# MCU.net
KiCad netlist of a schematic drawn in Altium Designer
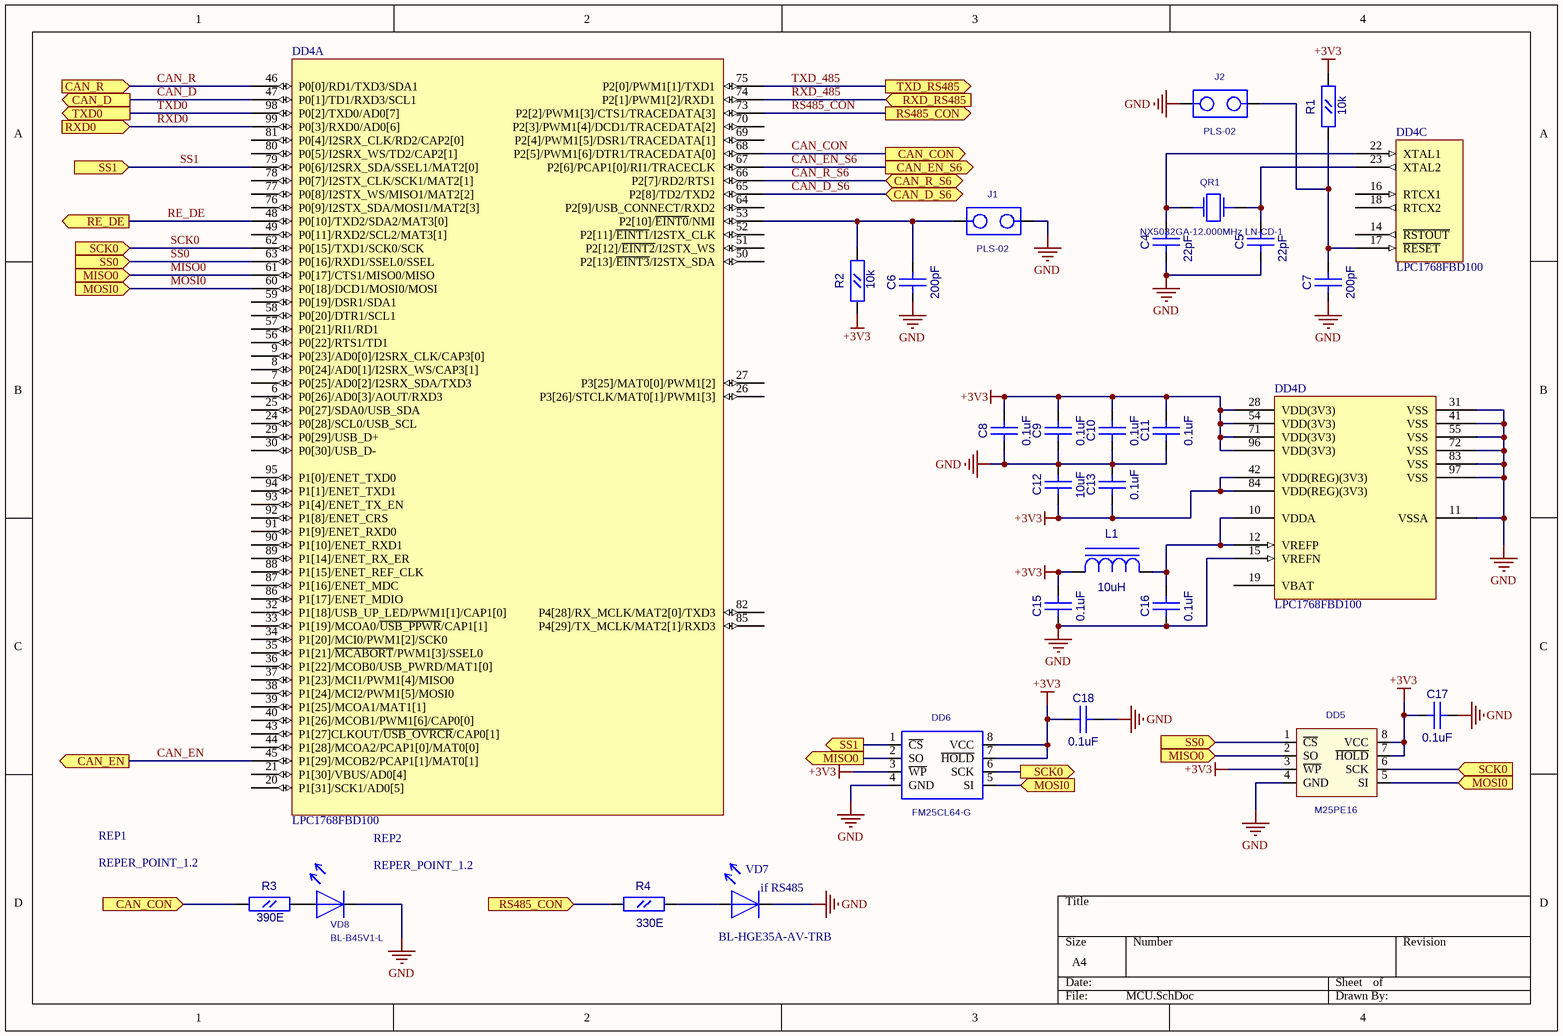
[diagram p0: MCU.SchDoc]

(export (version "E")
  (design (tool "Eeschema 10.0.6"))
  (components
    (comp (ref "C4")
      (value "22pF")
      (footprint "CC0603")
      (description "CC0603")
      (libsource (lib "gprs_modem_2") (part "CC0603"))
    )
    (comp (ref "C5")
      (value "22pF")
      (footprint "CC0603")
      (description "CC0603")
      (libsource (lib "gprs_modem_2") (part "CC0603"))
    )
    (comp (ref "C6")
      (value "200pF")
      (footprint "CC0603")
      (description "CC0603")
      (libsource (lib "gprs_modem_2") (part "CC0603"))
    )
    (comp (ref "C7")
      (value "200pF")
      (footprint "CC0603")
      (description "CC0603")
      (libsource (lib "gprs_modem_2") (part "CC0603"))
    )
    (comp (ref "C8")
      (value "0.1uF")
      (footprint "CC0603")
      (description "CC0603")
      (libsource (lib "gprs_modem_2") (part "CC0603"))
    )
    (comp (ref "C9")
      (value "0.1uF")
      (footprint "CC0603")
      (description "CC0603")
      (libsource (lib "gprs_modem_2") (part "CC0603"))
    )
    (comp (ref "C10")
      (value "0.1uF")
      (footprint "CC0603")
      (description "CC0603")
      (libsource (lib "gprs_modem_2") (part "CC0603"))
    )
    (comp (ref "C11")
      (value "0.1uF")
      (footprint "CC0603")
      (description "CC0603")
      (libsource (lib "gprs_modem_2") (part "CC0603"))
    )
    (comp (ref "C12")
      (value "10uF")
      (footprint "CC0805")
      (description "CC0805")
      (libsource (lib "gprs_modem_2") (part "CC0805"))
    )
    (comp (ref "C13")
      (value "0.1uF")
      (footprint "CC0603")
      (description "CC0603")
      (libsource (lib "gprs_modem_2") (part "CC0603"))
    )
    (comp (ref "C15")
      (value "0.1uF")
      (footprint "CC0603")
      (description "CC0603")
      (libsource (lib "gprs_modem_2") (part "CC0603"))
    )
    (comp (ref "C16")
      (value "0.1uF")
      (footprint "CC0603")
      (description "CC0603")
      (libsource (lib "gprs_modem_2") (part "CC0603"))
    )
    (comp (ref "C17")
      (value "0.1uF")
      (footprint "CC0603")
      (description "CC0603")
      (libsource (lib "gprs_modem_2") (part "CC0603"))
    )
    (comp (ref "C18")
      (value "0.1uF")
      (footprint "CC0603-3M")
      (description "CC0603")
      (libsource (lib "gprs_modem_2") (part "CC0603"))
    )
    (comp (ref "DD4")
      (value "LPC1768FBD100")
      (footprint "TQFP-100")
      (description "Cortex -M3 32-Bit Microcontroller, 512KB Flash, 64KB RAM, 100-Lead LQFP")
      (libsource (lib "gprs_modem_2") (part "LPC1768FBD100"))
    )
    (comp (ref "DD5")
      (value "M25PE16")
      (footprint "EIAJ_SO8")
      (description "S25FL016A0LMFI01")
      (libsource (lib "gprs_modem_2") (part "S25FL016A0LMFI01"))
    )
    (comp (ref "DD6")
      (value "FM25CL64-G")
      (footprint "SO-8")
      (libsource (lib "gprs_modem_2") (part "FM25CL64-G"))
    )
    (comp (ref "J1") (value "PLS-02") (footprint "PLS-02") (libsource (lib "gprs_modem_2") (part "PLS-02")))
    (comp (ref "J2") (value "PLS-02") (footprint "PLS-02") (libsource (lib "gprs_modem_2") (part "PLS-02")))
    (comp (ref "L1")
      (value "10uH")
      (footprint "L0603")
      (description "L0603")
      (libsource (lib "gprs_modem_2") (part "L0603"))
    )
    (comp (ref "QR1")
      (value "NX5032GA-12.000MHz LN-CD-1")
      (footprint "AC5032_2")
      (description "AC5032/2")
      (libsource (lib "gprs_modem_2") (part "AC5032_2"))
    )
    (comp (ref "R1")
      (value "10k")
      (footprint "RC0603")
      (description "RC0603")
      (libsource (lib "gprs_modem_2") (part "RC0603"))
    )
    (comp (ref "R2")
      (value "10k")
      (footprint "RC0603")
      (description "RC0603")
      (libsource (lib "gprs_modem_2") (part "RC0603"))
    )
    (comp (ref "R3")
      (value "390E")
      (footprint "RC0603")
      (description "RC0603")
      (libsource (lib "gprs_modem_2") (part "RC0603"))
    )
    (comp (ref "R4")
      (value "330E")
      (footprint "RC0603")
      (description "RC0603")
      (libsource (lib "gprs_modem_2") (part "RC0603"))
    )
    (comp (ref "REP1")
      (value "REPER_POINT_1.2")
      (footprint "REPER1.2")
      (description "REPER1.2")
      (libsource (lib "gprs_modem_2") (part "REPER1.2"))
    )
    (comp (ref "REP2")
      (value "REPER_POINT_1.2")
      (footprint "REPER1.2")
      (description "REPER1.2")
      (libsource (lib "gprs_modem_2") (part "REPER1.2"))
    )
    (comp (ref "VD7")
      (value "BL-HGE35A-AV-TRB")
      (footprint "LED0805")
      (libsource (lib "gprs_modem_2") (part "LED_0805"))
    )
    (comp (ref "VD8")
      (value "BL-B45V1-L")
      (footprint "LED3")
      (description "LED_3")
      (libsource (lib "gprs_modem_2") (part "LED_3"))
    )
  )
  (nets
    (net (code "1") (name "+3V3") (class "Default")
      (node (ref "C10") (pin "2") (pinfunction "B_2") (pintype "passive"))
      (node (ref "C11") (pin "2") (pinfunction "B_2") (pintype "passive"))
      (node (ref "C12") (pin "1") (pinfunction "A_1") (pintype "passive"))
      (node (ref "C13") (pin "1") (pinfunction "A_1") (pintype "passive"))
      (node (ref "C15") (pin "2") (pinfunction "B_2") (pintype "passive"))
      (node (ref "C17") (pin "1") (pinfunction "A_1") (pintype "passive"))
      (node (ref "C18") (pin "1") (pinfunction "A_1") (pintype "passive"))
      (node (ref "C8") (pin "2") (pinfunction "B_2") (pintype "passive"))
      (node (ref "C9") (pin "2") (pinfunction "B_2") (pintype "passive"))
      (node (ref "DD4") (pin "28") (pinfunction "VDD(3V3)_28") (pintype "power_in"))
      (node (ref "DD4") (pin "42") (pinfunction "VDD(REG)(3V3)_42") (pintype "power_in"))
      (node (ref "DD4") (pin "54") (pinfunction "VDD(3V3)_54") (pintype "power_in"))
      (node (ref "DD4") (pin "71") (pinfunction "VDD(3V3)_71") (pintype "power_in"))
      (node (ref "DD4") (pin "84") (pinfunction "VDD(REG)(3V3)_84") (pintype "power_in"))
      (node (ref "DD4") (pin "96") (pinfunction "VDD(3V3)_96") (pintype "power_in"))
      (node (ref "DD5") (pin "3") (pinfunction "~{WP}_3") (pintype "passive"))
      (node (ref "DD5") (pin "7") (pinfunction "~{HOLD}_7") (pintype "passive"))
      (node (ref "DD5") (pin "8") (pinfunction "VCC_8") (pintype "passive"))
      (node (ref "DD6") (pin "3") (pinfunction "~{WP}_3") (pintype "passive"))
      (node (ref "DD6") (pin "7") (pinfunction "~{HOLD}_7") (pintype "passive"))
      (node (ref "DD6") (pin "8") (pinfunction "VCC_8") (pintype "passive"))
      (node (ref "L1") (pin "1") (pinfunction "A_1") (pintype "passive"))
      (node (ref "R1") (pin "2") (pinfunction "B_2") (pintype "passive"))
      (node (ref "R2") (pin "1") (pinfunction "A_1") (pintype "passive"))
    )
    (net (code "2") (name "/CAN_CON") (class "Default")
      (node (ref "DD4") (pin "68") (pinfunction "P2[5]/PWM1[6]/DTR1/TRACEDATA[0]_68") (pintype "bidirectional"))
      (node (ref "R3") (pin "1") (pinfunction "A_1") (pintype "passive"))
    )
    (net (code "3") (name "/CAN_D") (class "Default")
      (node (ref "DD4") (pin "47") (pinfunction "P0[1]/TD1/RXD3/SCL1_47") (pintype "bidirectional"))
    )
    (net (code "4") (name "/CAN_D_S6") (class "Default")
      (node (ref "DD4") (pin "65") (pinfunction "P2[8]/TD2/TXD2_65") (pintype "bidirectional"))
    )
    (net (code "5") (name "/CAN_EN") (class "Default")
      (node (ref "DD4") (pin "45") (pinfunction "P1[29]/MCOB2/PCAP1[1]/MAT0[1]_45") (pintype "bidirectional"))
    )
    (net (code "6") (name "/CAN_EN_S6") (class "Default")
      (node (ref "DD4") (pin "67") (pinfunction "P2[6]/PCAP1[0]/RI1/TRACECLK_67") (pintype "bidirectional"))
    )
    (net (code "7") (name "/CAN_R") (class "Default")
      (node (ref "DD4") (pin "46") (pinfunction "P0[0]/RD1/TXD3/SDA1_46") (pintype "bidirectional"))
    )
    (net (code "8") (name "/CAN_R_S6") (class "Default")
      (node (ref "DD4") (pin "66") (pinfunction "P2[7]/RD2/RTS1_66") (pintype "bidirectional"))
    )
    (net (code "9") (name "/MISO0") (class "Default")
      (node (ref "DD4") (pin "61") (pinfunction "P0[17]/CTS1/MISO0/MISO_61") (pintype "bidirectional"))
      (node (ref "DD5") (pin "2") (pinfunction "SO_2") (pintype "passive"))
      (node (ref "DD6") (pin "2") (pinfunction "SO_2") (pintype "passive"))
    )
    (net (code "10") (name "/MOSI0") (class "Default")
      (node (ref "DD4") (pin "60") (pinfunction "P0[18]/DCD1/MOSI0/MOSI_60") (pintype "bidirectional"))
      (node (ref "DD5") (pin "5") (pinfunction "SI_5") (pintype "passive"))
      (node (ref "DD6") (pin "5") (pinfunction "SI_5") (pintype "passive"))
    )
    (net (code "11") (name "/RE_DE") (class "Default")
      (node (ref "DD4") (pin "48") (pinfunction "P0[10]/TXD2/SDA2/MAT3[0]_48") (pintype "bidirectional"))
    )
    (net (code "12") (name "/RS485_CON") (class "Default")
      (node (ref "DD4") (pin "73") (pinfunction "P2[2]/PWM1[3]/CTS1/TRACEDATA[3]_73") (pintype "bidirectional"))
      (node (ref "R4") (pin "1") (pinfunction "A_1") (pintype "passive"))
    )
    (net (code "13") (name "/RXD0") (class "Default")
      (node (ref "DD4") (pin "99") (pinfunction "P0[3]/RXD0/AD0[6]_99") (pintype "bidirectional"))
    )
    (net (code "14") (name "/RXD_485") (class "Default")
      (node (ref "DD4") (pin "74") (pinfunction "P2[1]/PWM1[2]/RXD1_74") (pintype "bidirectional"))
    )
    (net (code "15") (name "/SCK0") (class "Default")
      (node (ref "DD4") (pin "62") (pinfunction "P0[15]/TXD1/SCK0/SCK_62") (pintype "bidirectional"))
      (node (ref "DD5") (pin "6") (pinfunction "SCK_6") (pintype "passive"))
      (node (ref "DD6") (pin "6") (pinfunction "SCK_6") (pintype "passive"))
    )
    (net (code "16") (name "/SS0") (class "Default")
      (node (ref "DD4") (pin "63") (pinfunction "P0[16]/RXD1/SSEL0/SSEL_63") (pintype "bidirectional"))
      (node (ref "DD5") (pin "1") (pinfunction "~{CS}_1") (pintype "passive"))
    )
    (net (code "17") (name "/SS1") (class "Default")
      (node (ref "DD4") (pin "79") (pinfunction "P0[6]/I2SRX_SDA/SSEL1/MAT2[0]_79") (pintype "bidirectional"))
      (node (ref "DD6") (pin "1") (pinfunction "~{CS}_1") (pintype "passive"))
    )
    (net (code "18") (name "/TXD0") (class "Default")
      (node (ref "DD4") (pin "98") (pinfunction "P0[2]/TXD0/AD0[7]_98") (pintype "bidirectional"))
    )
    (net (code "19") (name "/TXD_485") (class "Default")
      (node (ref "DD4") (pin "75") (pinfunction "P2[0]/PWM1[1]/TXD1_75") (pintype "bidirectional"))
    )
    (net (code "20") (name "GND") (class "Default")
      (node (ref "C10") (pin "1") (pinfunction "A_1") (pintype "passive"))
      (node (ref "C11") (pin "1") (pinfunction "A_1") (pintype "passive"))
      (node (ref "C12") (pin "2") (pinfunction "B_2") (pintype "passive"))
      (node (ref "C13") (pin "2") (pinfunction "B_2") (pintype "passive"))
      (node (ref "C15") (pin "1") (pinfunction "A_1") (pintype "passive"))
      (node (ref "C16") (pin "1") (pinfunction "A_1") (pintype "passive"))
      (node (ref "C17") (pin "2") (pinfunction "B_2") (pintype "passive"))
      (node (ref "C18") (pin "2") (pinfunction "B_2") (pintype "passive"))
      (node (ref "C4") (pin "1") (pinfunction "A_1") (pintype "passive"))
      (node (ref "C5") (pin "1") (pinfunction "A_1") (pintype "passive"))
      (node (ref "C6") (pin "1") (pinfunction "A_1") (pintype "passive"))
      (node (ref "C7") (pin "1") (pinfunction "A_1") (pintype "passive"))
      (node (ref "C8") (pin "1") (pinfunction "A_1") (pintype "passive"))
      (node (ref "C9") (pin "1") (pinfunction "A_1") (pintype "passive"))
      (node (ref "DD4") (pin "11") (pinfunction "VSSA_11") (pintype "power_in"))
      (node (ref "DD4") (pin "15") (pinfunction "VREFN_15") (pintype "input"))
      (node (ref "DD4") (pin "31") (pinfunction "VSS_31") (pintype "power_in"))
      (node (ref "DD4") (pin "41") (pinfunction "VSS_41") (pintype "power_in"))
      (node (ref "DD4") (pin "55") (pinfunction "VSS_55") (pintype "power_in"))
      (node (ref "DD4") (pin "72") (pinfunction "VSS_72") (pintype "power_in"))
      (node (ref "DD4") (pin "83") (pinfunction "VSS_83") (pintype "power_in"))
      (node (ref "DD4") (pin "97") (pinfunction "VSS_97") (pintype "power_in"))
      (node (ref "DD5") (pin "4") (pinfunction "GND_4") (pintype "passive"))
      (node (ref "DD6") (pin "4") (pinfunction "GND_4") (pintype "passive"))
      (node (ref "J1") (pin "2") (pintype "passive"))
      (node (ref "J2") (pin "1") (pintype "passive"))
      (node (ref "VD7") (pin "2") (pintype "passive"))
      (node (ref "VD8") (pin "1") (pintype "passive"))
    )
    (net (code "21") (name "Net-(C4-B)") (class "Default")
      (node (ref "C4") (pin "2") (pinfunction "B_2") (pintype "passive"))
      (node (ref "DD4") (pin "22") (pinfunction "XTAL1_22") (pintype "input"))
      (node (ref "QR1") (pin "1") (pintype "passive"))
    )
    (net (code "22") (name "Net-(C5-B)") (class "Default")
      (node (ref "C5") (pin "2") (pinfunction "B_2") (pintype "passive"))
      (node (ref "DD4") (pin "23") (pinfunction "XTAL2_23") (pintype "output"))
      (node (ref "QR1") (pin "2") (pintype "passive"))
    )
    (net (code "23") (name "Net-(C6-B)") (class "Default")
      (node (ref "C6") (pin "2") (pinfunction "B_2") (pintype "passive"))
      (node (ref "DD4") (pin "53") (pinfunction "P2[10]/~{EINT0}/NMI_53") (pintype "bidirectional"))
      (node (ref "J1") (pin "1") (pintype "passive"))
      (node (ref "R2") (pin "2") (pinfunction "B_2") (pintype "passive"))
    )
    (net (code "24") (name "Net-(C7-B)") (class "Default")
      (node (ref "C7") (pin "2") (pinfunction "B_2") (pintype "passive"))
      (node (ref "DD4") (pin "17") (pinfunction "~{RESET}_17") (pintype "input"))
      (node (ref "J2") (pin "2") (pintype "passive"))
      (node (ref "R1") (pin "1") (pinfunction "A_1") (pintype "passive"))
    )
    (net (code "25") (name "Net-(C16-B)") (class "Default")
      (node (ref "C16") (pin "2") (pinfunction "B_2") (pintype "passive"))
      (node (ref "DD4") (pin "10") (pinfunction "VDDA_10") (pintype "power_in"))
      (node (ref "DD4") (pin "12") (pinfunction "VREFP_12") (pintype "input"))
      (node (ref "L1") (pin "2") (pinfunction "C_2") (pintype "passive"))
    )
    (net (code "26") (name "Net-(R3-B)") (class "Default")
      (node (ref "R3") (pin "2") (pinfunction "B_2") (pintype "passive"))
      (node (ref "VD8") (pin "2") (pintype "passive"))
    )
    (net (code "27") (name "Net-(R4-B)") (class "Default")
      (node (ref "R4") (pin "2") (pinfunction "B_2") (pintype "passive"))
      (node (ref "VD7") (pin "1") (pintype "passive"))
    )
    (net (code "28") (name "unconnected-(DD4A-P0[4]{slash}I2SRX_CLK{slash}RD2{slash}CAP2[0]-Pad81)") (class "Default")
      (node (ref "DD4") (pin "81") (pinfunction "P0[4]/I2SRX_CLK/RD2/CAP2[0]_81") (pintype "bidirectional"))
    )
    (net (code "29") (name "unconnected-(DD4A-P0[5]{slash}I2SRX_WS{slash}TD2{slash}CAP2[1]-Pad80)") (class "Default")
      (node (ref "DD4") (pin "80") (pinfunction "P0[5]/I2SRX_WS/TD2/CAP2[1]_80") (pintype "bidirectional"))
    )
    (net (code "30") (name "unconnected-(DD4A-P0[7]{slash}I2STX_CLK{slash}SCK1{slash}MAT2[1]-Pad78)") (class "Default")
      (node (ref "DD4") (pin "78") (pinfunction "P0[7]/I2STX_CLK/SCK1/MAT2[1]_78") (pintype "bidirectional"))
    )
    (net (code "31") (name "unconnected-(DD4A-P0[8]{slash}I2STX_WS{slash}MISO1{slash}MAT2[2]-Pad77)") (class "Default")
      (node (ref "DD4") (pin "77") (pinfunction "P0[8]/I2STX_WS/MISO1/MAT2[2]_77") (pintype "bidirectional"))
    )
    (net (code "32") (name "unconnected-(DD4A-P0[9]{slash}I2STX_SDA{slash}MOSI1{slash}MAT2[3]-Pad76)") (class "Default")
      (node (ref "DD4") (pin "76") (pinfunction "P0[9]/I2STX_SDA/MOSI1/MAT2[3]_76") (pintype "bidirectional"))
    )
    (net (code "33") (name "unconnected-(DD4A-P0[11]{slash}RXD2{slash}SCL2{slash}MAT3[1]-Pad49)") (class "Default")
      (node (ref "DD4") (pin "49") (pinfunction "P0[11]/RXD2/SCL2/MAT3[1]_49") (pintype "bidirectional"))
    )
    (net (code "34") (name "unconnected-(DD4A-P0[19]{slash}DSR1{slash}SDA1-Pad59)") (class "Default")
      (node (ref "DD4") (pin "59") (pinfunction "P0[19]/DSR1/SDA1_59") (pintype "bidirectional"))
    )
    (net (code "35") (name "unconnected-(DD4A-P0[20]{slash}DTR1{slash}SCL1-Pad58)") (class "Default")
      (node (ref "DD4") (pin "58") (pinfunction "P0[20]/DTR1/SCL1_58") (pintype "bidirectional"))
    )
    (net (code "36") (name "unconnected-(DD4A-P0[21]{slash}RI1{slash}RD1-Pad57)") (class "Default")
      (node (ref "DD4") (pin "57") (pinfunction "P0[21]/RI1/RD1_57") (pintype "bidirectional"))
    )
    (net (code "37") (name "unconnected-(DD4A-P0[22]{slash}RTS1{slash}TD1-Pad56)") (class "Default")
      (node (ref "DD4") (pin "56") (pinfunction "P0[22]/RTS1/TD1_56") (pintype "bidirectional"))
    )
    (net (code "38") (name "unconnected-(DD4A-P0[23]{slash}AD0[0]{slash}I2SRX_CLK{slash}CAP3[0]-Pad9)") (class "Default")
      (node (ref "DD4") (pin "9") (pinfunction "P0[23]/AD0[0]/I2SRX_CLK/CAP3[0]_9") (pintype "bidirectional"))
    )
    (net (code "39") (name "unconnected-(DD4A-P0[24]{slash}AD0[1]{slash}I2SRX_WS{slash}CAP3[1]-Pad8)") (class "Default")
      (node (ref "DD4") (pin "8") (pinfunction "P0[24]/AD0[1]/I2SRX_WS/CAP3[1]_8") (pintype "bidirectional"))
    )
    (net (code "40") (name "unconnected-(DD4A-P0[25]{slash}AD0[2]{slash}I2SRX_SDA{slash}TXD3-Pad7)") (class "Default")
      (node (ref "DD4") (pin "7") (pinfunction "P0[25]/AD0[2]/I2SRX_SDA/TXD3_7") (pintype "bidirectional"))
    )
    (net (code "41") (name "unconnected-(DD4A-P0[26]{slash}AD0[3]{slash}AOUT{slash}RXD3-Pad6)") (class "Default")
      (node (ref "DD4") (pin "6") (pinfunction "P0[26]/AD0[3]/AOUT/RXD3_6") (pintype "bidirectional"))
    )
    (net (code "42") (name "unconnected-(DD4A-P0[27]{slash}SDA0{slash}USB_SDA-Pad25)") (class "Default")
      (node (ref "DD4") (pin "25") (pinfunction "P0[27]/SDA0/USB_SDA_25") (pintype "bidirectional"))
    )
    (net (code "43") (name "unconnected-(DD4A-P0[28]{slash}SCL0{slash}USB_SCL-Pad24)") (class "Default")
      (node (ref "DD4") (pin "24") (pinfunction "P0[28]/SCL0/USB_SCL_24") (pintype "bidirectional"))
    )
    (net (code "44") (name "unconnected-(DD4A-P0[29]{slash}USB_D+-Pad29)") (class "Default")
      (node (ref "DD4") (pin "29") (pinfunction "P0[29]/USB_D+_29") (pintype "bidirectional"))
    )
    (net (code "45") (name "unconnected-(DD4A-P0[30]{slash}USB_D--Pad30)") (class "Default")
      (node (ref "DD4") (pin "30") (pinfunction "P0[30]/USB_D-_30") (pintype "bidirectional"))
    )
    (net (code "46") (name "unconnected-(DD4A-P1[0]{slash}ENET_TXD0-Pad95)") (class "Default")
      (node (ref "DD4") (pin "95") (pinfunction "P1[0]/ENET_TXD0_95") (pintype "bidirectional"))
    )
    (net (code "47") (name "unconnected-(DD4A-P1[1]{slash}ENET_TXD1-Pad94)") (class "Default")
      (node (ref "DD4") (pin "94") (pinfunction "P1[1]/ENET_TXD1_94") (pintype "bidirectional"))
    )
    (net (code "48") (name "unconnected-(DD4A-P1[4]{slash}ENET_TX_EN-Pad93)") (class "Default")
      (node (ref "DD4") (pin "93") (pinfunction "P1[4]/ENET_TX_EN_93") (pintype "bidirectional"))
    )
    (net (code "49") (name "unconnected-(DD4A-P1[8]{slash}ENET_CRS-Pad92)") (class "Default")
      (node (ref "DD4") (pin "92") (pinfunction "P1[8]/ENET_CRS_92") (pintype "bidirectional"))
    )
    (net (code "50") (name "unconnected-(DD4A-P1[9]{slash}ENET_RXD0-Pad91)") (class "Default")
      (node (ref "DD4") (pin "91") (pinfunction "P1[9]/ENET_RXD0_91") (pintype "bidirectional"))
    )
    (net (code "51") (name "unconnected-(DD4A-P1[10]{slash}ENET_RXD1-Pad90)") (class "Default")
      (node (ref "DD4") (pin "90") (pinfunction "P1[10]/ENET_RXD1_90") (pintype "bidirectional"))
    )
    (net (code "52") (name "unconnected-(DD4A-P1[14]{slash}ENET_RX_ER-Pad89)") (class "Default")
      (node (ref "DD4") (pin "89") (pinfunction "P1[14]/ENET_RX_ER_89") (pintype "bidirectional"))
    )
    (net (code "53") (name "unconnected-(DD4A-P1[15]{slash}ENET_REF_CLK-Pad88)") (class "Default")
      (node (ref "DD4") (pin "88") (pinfunction "P1[15]/ENET_REF_CLK_88") (pintype "bidirectional"))
    )
    (net (code "54") (name "unconnected-(DD4A-P1[16]{slash}ENET_MDC-Pad87)") (class "Default")
      (node (ref "DD4") (pin "87") (pinfunction "P1[16]/ENET_MDC_87") (pintype "bidirectional"))
    )
    (net (code "55") (name "unconnected-(DD4A-P1[17]{slash}ENET_MDIO-Pad86)") (class "Default")
      (node (ref "DD4") (pin "86") (pinfunction "P1[17]/ENET_MDIO_86") (pintype "bidirectional"))
    )
    (net (code "56") (name "unconnected-(DD4A-P1[18]{slash}USB_UP_LED{slash}PWM1[1]{slash}CAP1[0]-Pad32)") (class "Default")
      (node (ref "DD4") (pin "32") (pinfunction "P1[18]/USB_UP_LED/PWM1[1]/CAP1[0]_32") (pintype "bidirectional"))
    )
    (net (code "57") (name "unconnected-(DD4A-P1[19]{slash}MCOA0{slash}~{USB_PPWR}{slash}CAP1[1]-Pad33)") (class "Default")
      (node (ref "DD4") (pin "33") (pinfunction "P1[19]/MCOA0/~{USB_PPWR}/CAP1[1]_33") (pintype "bidirectional"))
    )
    (net (code "58") (name "unconnected-(DD4A-P1[20]{slash}MCI0{slash}PWM1[2]{slash}SCK0-Pad34)") (class "Default")
      (node (ref "DD4") (pin "34") (pinfunction "P1[20]/MCI0/PWM1[2]/SCK0_34") (pintype "bidirectional"))
    )
    (net (code "59") (name "unconnected-(DD4A-P1[21]{slash}~{MCABORT}{slash}PWM1[3]{slash}SSEL0-Pad35)") (class "Default")
      (node (ref "DD4") (pin "35") (pinfunction "P1[21]/~{MCABORT}/PWM1[3]/SSEL0_35") (pintype "bidirectional"))
    )
    (net (code "60") (name "unconnected-(DD4A-P1[22]{slash}MCOB0{slash}USB_PWRD{slash}MAT1[0]-Pad36)") (class "Default")
      (node (ref "DD4") (pin "36") (pinfunction "P1[22]/MCOB0/USB_PWRD/MAT1[0]_36") (pintype "bidirectional"))
    )
    (net (code "61") (name "unconnected-(DD4A-P1[23]{slash}MCI1{slash}PWM1[4]{slash}MISO0-Pad37)") (class "Default")
      (node (ref "DD4") (pin "37") (pinfunction "P1[23]/MCI1/PWM1[4]/MISO0_37") (pintype "bidirectional"))
    )
    (net (code "62") (name "unconnected-(DD4A-P1[24]{slash}MCI2{slash}PWM1[5]{slash}MOSI0-Pad38)") (class "Default")
      (node (ref "DD4") (pin "38") (pinfunction "P1[24]/MCI2/PWM1[5]/MOSI0_38") (pintype "bidirectional"))
    )
    (net (code "63") (name "unconnected-(DD4A-P1[25]{slash}MCOA1{slash}MAT1[1]-Pad39)") (class "Default")
      (node (ref "DD4") (pin "39") (pinfunction "P1[25]/MCOA1/MAT1[1]_39") (pintype "bidirectional"))
    )
    (net (code "64") (name "unconnected-(DD4A-P1[26]{slash}MCOB1{slash}PWM1[6]{slash}CAP0[0]-Pad40)") (class "Default")
      (node (ref "DD4") (pin "40") (pinfunction "P1[26]/MCOB1/PWM1[6]/CAP0[0]_40") (pintype "bidirectional"))
    )
    (net (code "65") (name "unconnected-(DD4A-P1[27]CLKOUT{slash}~{USB_OVRCR}{slash}CAP0[1]-Pad43)") (class "Default")
      (node (ref "DD4") (pin "43") (pinfunction "P1[27]CLKOUT/~{USB_OVRCR}/CAP0[1]_43") (pintype "bidirectional"))
    )
    (net (code "66") (name "unconnected-(DD4A-P1[28]{slash}MCOA2{slash}PCAP1[0]{slash}MAT0[0]-Pad44)") (class "Default")
      (node (ref "DD4") (pin "44") (pinfunction "P1[28]/MCOA2/PCAP1[0]/MAT0[0]_44") (pintype "bidirectional"))
    )
    (net (code "67") (name "unconnected-(DD4A-P1[30]{slash}VBUS{slash}AD0[4]-Pad21)") (class "Default")
      (node (ref "DD4") (pin "21") (pinfunction "P1[30]/VBUS/AD0[4]_21") (pintype "bidirectional"))
    )
    (net (code "68") (name "unconnected-(DD4A-P1[31]{slash}SCK1{slash}AD0[5]-Pad20)") (class "Default")
      (node (ref "DD4") (pin "20") (pinfunction "P1[31]/SCK1/AD0[5]_20") (pintype "bidirectional"))
    )
    (net (code "69") (name "unconnected-(DD4A-P2[3]{slash}PWM1[4]{slash}DCD1{slash}TRACEDATA[2]-Pad70)") (class "Default")
      (node (ref "DD4") (pin "70") (pinfunction "P2[3]/PWM1[4]/DCD1/TRACEDATA[2]_70") (pintype "bidirectional"))
    )
    (net (code "70") (name "unconnected-(DD4A-P2[4]{slash}PWM1[5]{slash}DSR1{slash}TRACEDATA[1]-Pad69)") (class "Default")
      (node (ref "DD4") (pin "69") (pinfunction "P2[4]/PWM1[5]/DSR1/TRACEDATA[1]_69") (pintype "bidirectional"))
    )
    (net (code "71") (name "unconnected-(DD4A-P2[9]{slash}USB_CONNECT{slash}RXD2-Pad64)") (class "Default")
      (node (ref "DD4") (pin "64") (pinfunction "P2[9]/USB_CONNECT/RXD2_64") (pintype "bidirectional"))
    )
    (net (code "72") (name "unconnected-(DD4A-P2[11]{slash}~{EINT1}{slash}I2STX_CLK-Pad52)") (class "Default")
      (node (ref "DD4") (pin "52") (pinfunction "P2[11]/~{EINT1}/I2STX_CLK_52") (pintype "bidirectional"))
    )
    (net (code "73") (name "unconnected-(DD4A-P2[12]{slash}~{EINT2}{slash}I2STX_WS-Pad51)") (class "Default")
      (node (ref "DD4") (pin "51") (pinfunction "P2[12]/~{EINT2}/I2STX_WS_51") (pintype "bidirectional"))
    )
    (net (code "74") (name "unconnected-(DD4A-P2[13]{slash}~{EINT3}{slash}I2STX_SDA-Pad50)") (class "Default")
      (node (ref "DD4") (pin "50") (pinfunction "P2[13]/~{EINT3}/I2STX_SDA_50") (pintype "bidirectional"))
    )
    (net (code "75") (name "unconnected-(DD4A-P3[25]{slash}MAT0[0]{slash}PWM1[2]-Pad27)") (class "Default")
      (node (ref "DD4") (pin "27") (pinfunction "P3[25]/MAT0[0]/PWM1[2]_27") (pintype "bidirectional"))
    )
    (net (code "76") (name "unconnected-(DD4A-P3[26]{slash}STCLK{slash}MAT0[1]{slash}PWM1[3]-Pad26)") (class "Default")
      (node (ref "DD4") (pin "26") (pinfunction "P3[26]/STCLK/MAT0[1]/PWM1[3]_26") (pintype "bidirectional"))
    )
    (net (code "77") (name "unconnected-(DD4A-P4[28]{slash}RX_MCLK{slash}MAT2[0]{slash}TXD3-Pad82)") (class "Default")
      (node (ref "DD4") (pin "82") (pinfunction "P4[28]/RX_MCLK/MAT2[0]/TXD3_82") (pintype "bidirectional"))
    )
    (net (code "78") (name "unconnected-(DD4A-P4[29]{slash}TX_MCLK{slash}MAT2[1]{slash}RXD3-Pad85)") (class "Default")
      (node (ref "DD4") (pin "85") (pinfunction "P4[29]/TX_MCLK/MAT2[1]/RXD3_85") (pintype "bidirectional"))
    )
    (net (code "79") (name "unconnected-(DD4C-RTCX1-Pad16)") (class "Default")
      (node (ref "DD4") (pin "16") (pinfunction "RTCX1_16") (pintype "input"))
    )
    (net (code "80") (name "unconnected-(DD4C-RTCX2-Pad18)") (class "Default")
      (node (ref "DD4") (pin "18") (pinfunction "RTCX2_18") (pintype "output"))
    )
    (net (code "81") (name "unconnected-(DD4C-~{RSTOUT}-Pad14)") (class "Default")
      (node (ref "DD4") (pin "14") (pinfunction "~{RSTOUT}_14") (pintype "output"))
    )
    (net (code "82") (name "unconnected-(DD4D-VBAT-Pad19)") (class "Default")
      (node (ref "DD4") (pin "19") (pinfunction "VBAT_19") (pintype "power_in"))
    )
    (net (code "83") (name "unconnected-(REP1-Pad1)") (class "Default")
      (node (ref "REP1") (pin "1") (pintype "passive"))
    )
    (net (code "84") (name "unconnected-(REP2-Pad1)") (class "Default")
      (node (ref "REP2") (pin "1") (pintype "passive"))
    )
  )
)
